# altium.net
KiCad netlist of a schematic drawn in Altium Designer
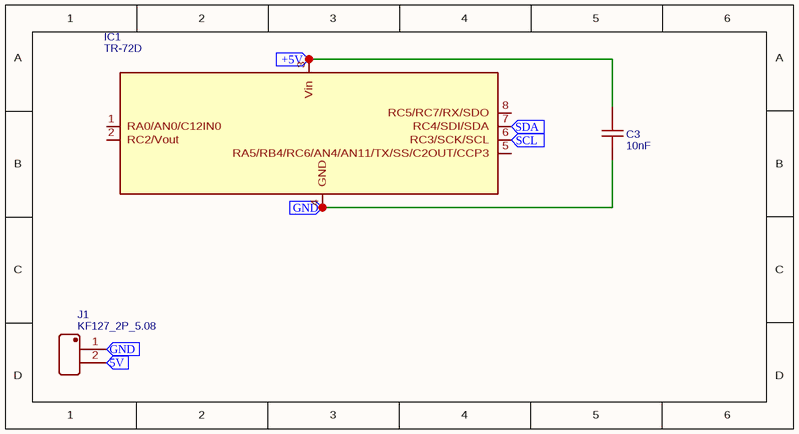
[diagram p0: altium.schdoc]

(export (version "E")
  (design (tool "Eeschema 10.0.6"))
  (components
    (comp (ref "C3")
      (value "10nF")
      (fields
        (field (name "BOM_SUPPLIER PART") "C327421")
        (field (name "BOM_MANUFACTURER PART") "0603B103K500AT")
        (field (name "CONTRIBUTOR") "LCSC")
      )
      (libsource (lib "altium-import") (part "root_0_10nF_"))
    )
    (comp (ref "IC1")
      (value "TR-72D")
      (fields (field (name "CONTRIBUTOR") "Simen Stensas"))
      (libsource (lib "altium-import") (part "root_0_TR-72D_"))
    )
    (comp (ref "J1")
      (value "KF127_2P_5.08")
      (fields (field (name "BOM_MANUFACTURER PART") "KF127L-5.08") (field (name "CONTRIBUTOR") "GrahamG"))
      (libsource (lib "altium-import") (part "root_0_KF127_2P_5.08_"))
    )
  )
  (nets
    (net (code "1") (name "/+5V") (class "Default")
      (node (ref "C3") (pin "2") (pinfunction "2_2") (pintype "passive"))
      (node (ref "IC1") (pin "3") (pinfunction "Vin_3") (pintype "passive"))
    )
    (net (code "2") (name "/5V") (class "Default")
      (node (ref "J1") (pin "2") (pinfunction "PIN2_2") (pintype "passive"))
    )
    (net (code "3") (name "/GND") (class "Default")
      (node (ref "C3") (pin "1") (pinfunction "1_1") (pintype "passive"))
      (node (ref "IC1") (pin "4") (pinfunction "GND_4") (pintype "passive"))
      (node (ref "J1") (pin "1") (pinfunction "PIN1_1") (pintype "passive"))
    )
    (net (code "4") (name "/SCL") (class "Default")
      (node (ref "IC1") (pin "6") (pinfunction "RC3/SCK/SCL_6") (pintype "passive"))
    )
    (net (code "5") (name "/SDA") (class "Default")
      (node (ref "IC1") (pin "7") (pinfunction "RC4/SDI/SDA_7") (pintype "passive"))
    )
    (net (code "6") (name "unconnected-(IC1-RA0{slash}AN0{slash}C12IN0-Pad1)") (class "Default")
      (node (ref "IC1") (pin "1") (pinfunction "RA0/AN0/C12IN0_1") (pintype "passive"))
    )
    (net (code "7") (name "unconnected-(IC1-RA5{slash}RB4{slash}RC6{slash}AN4{slash}AN11{slash}TX{slash}SS{slash}C2OUT{slash}CCP3-Pad5)") (class "Default")
      (node (ref "IC1") (pin "5") (pinfunction "RA5/RB4/RC6/AN4/AN11/TX/SS/C2OUT/CCP3_5") (pintype "passive"))
    )
    (net (code "8") (name "unconnected-(IC1-RC2{slash}Vout-Pad2)") (class "Default")
      (node (ref "IC1") (pin "2") (pinfunction "RC2/Vout_2") (pintype "passive"))
    )
    (net (code "9") (name "unconnected-(IC1-RC5{slash}RC7{slash}RX{slash}SDO-Pad8)") (class "Default")
      (node (ref "IC1") (pin "8") (pinfunction "RC5/RC7/RX/SDO_8") (pintype "passive"))
    )
  )
)
